# PCB.net
KiCad netlist of a schematic drawn in EasyEDA Pro
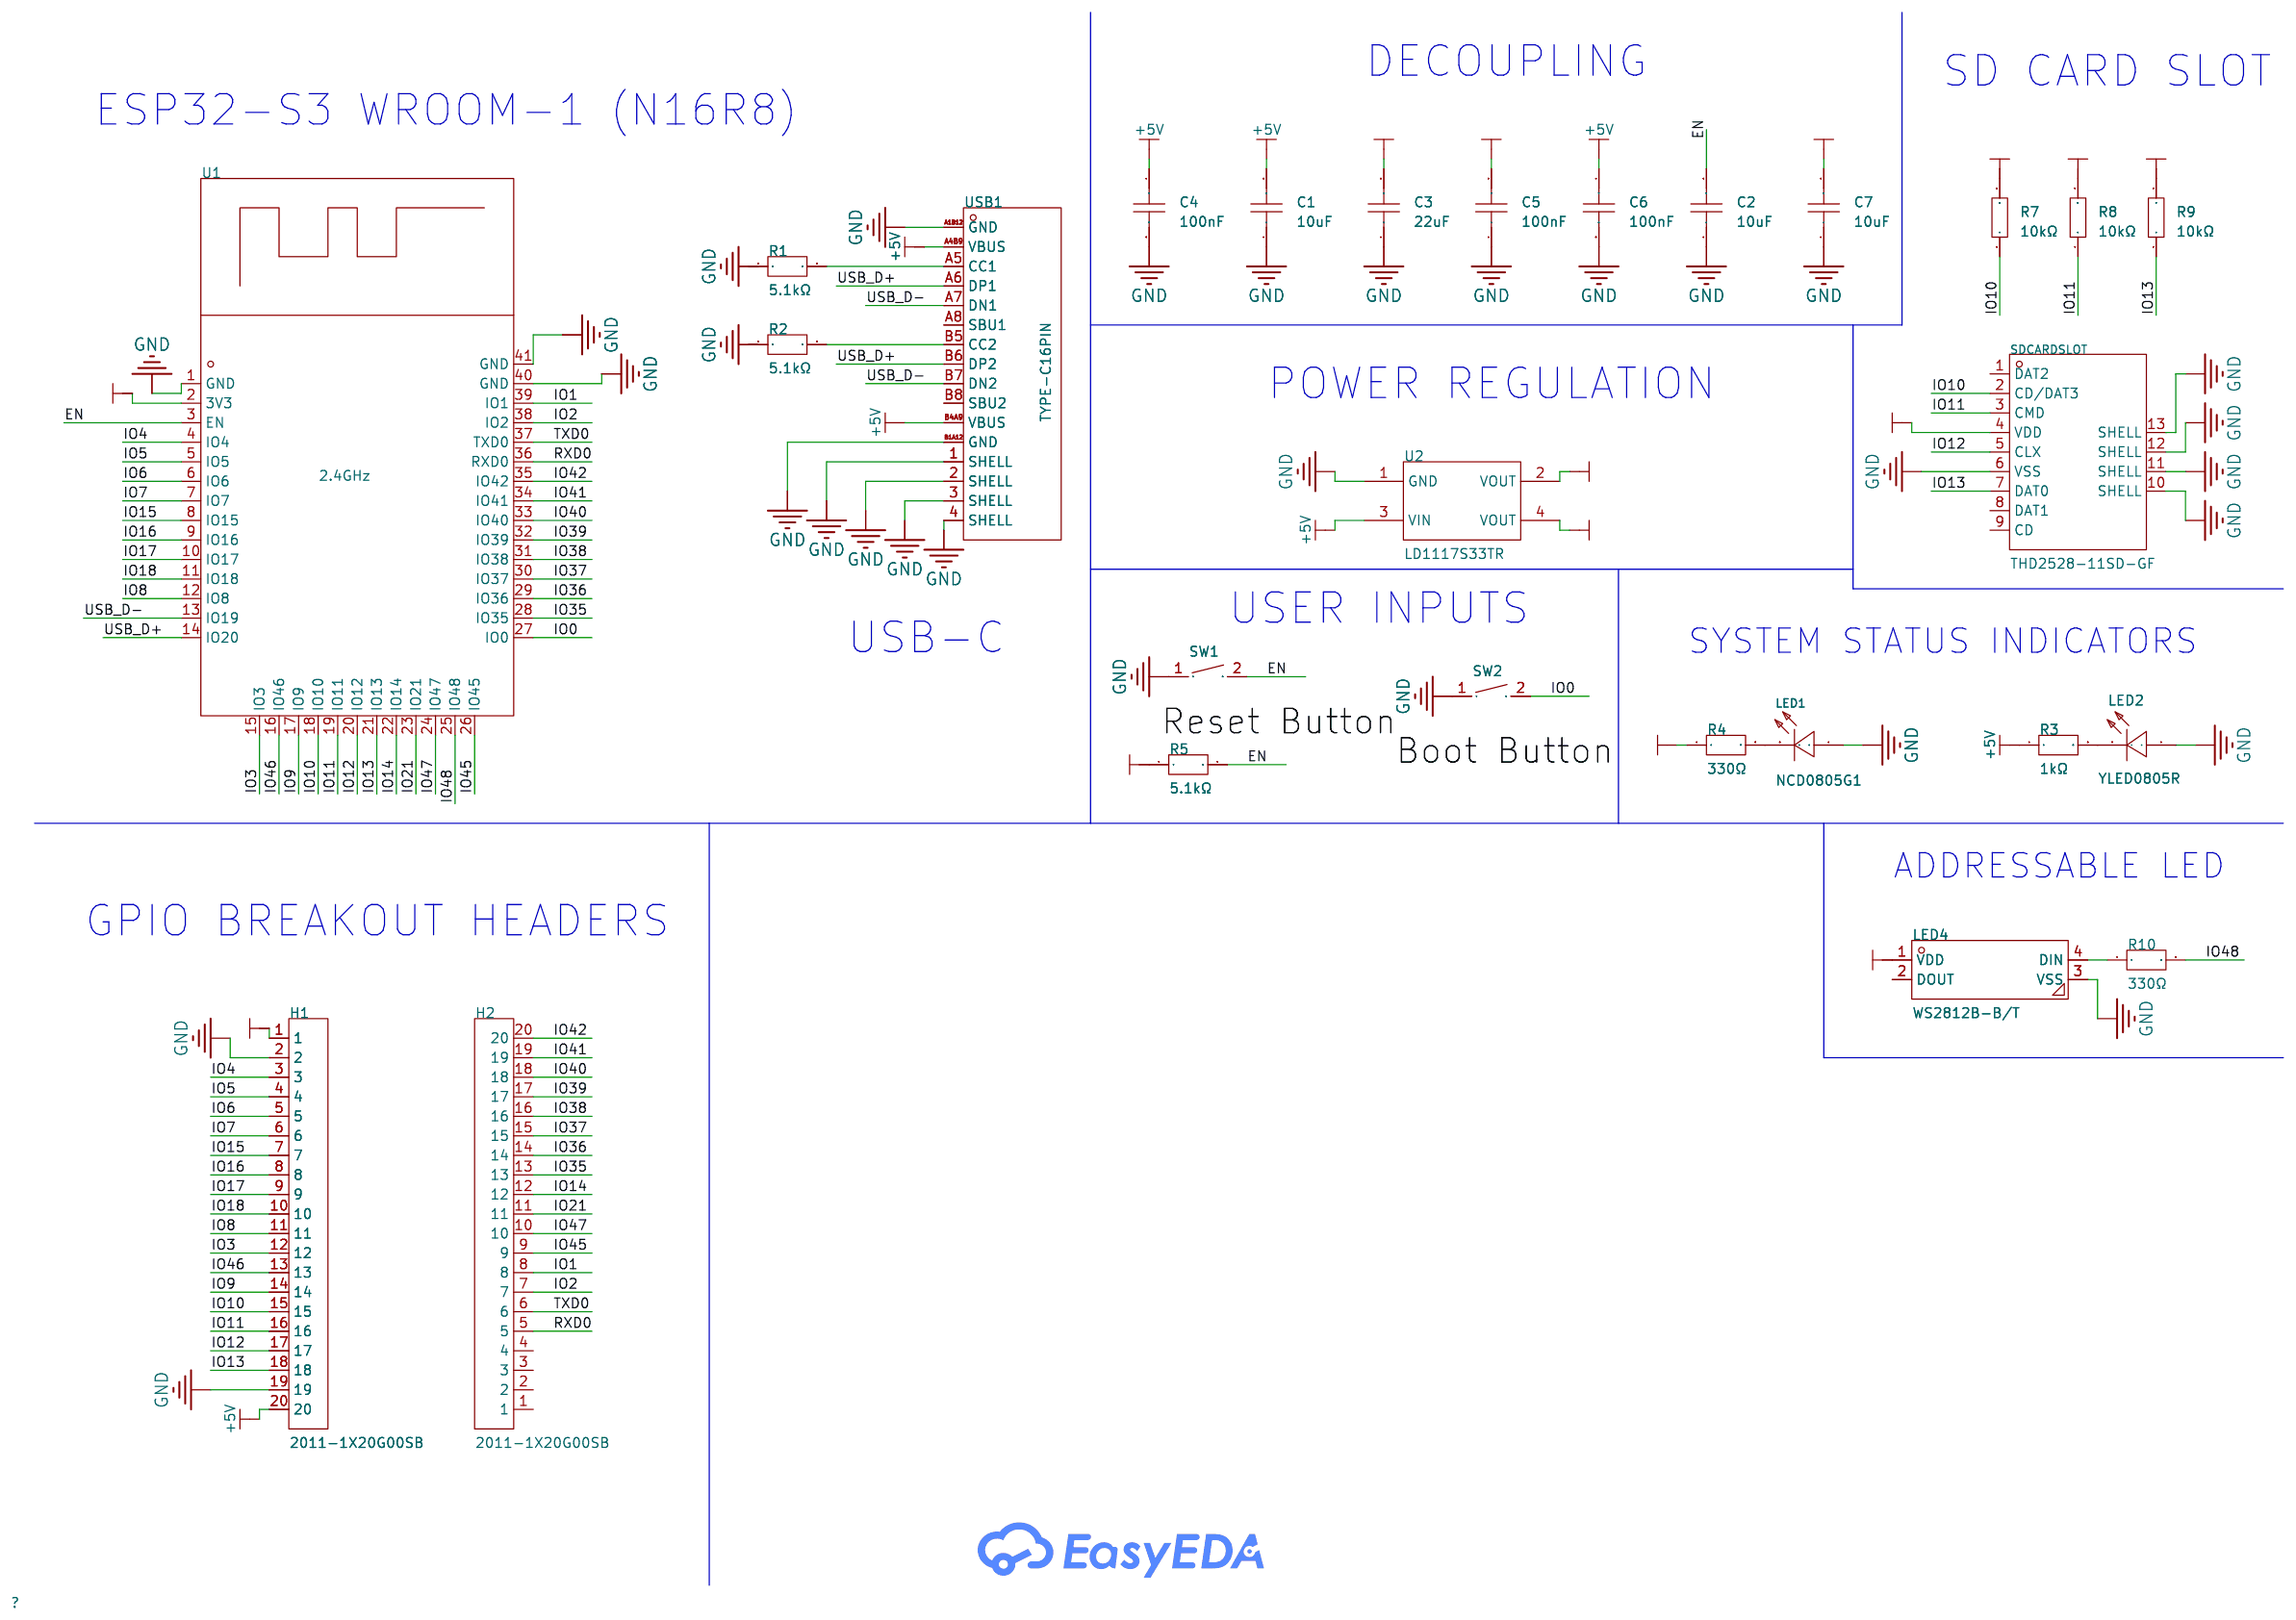
[diagram p0: schematic sheet]

(export (version "E")
  (design (tool "Eeschema 10.0.6"))
  (components
    (comp (ref "C1")
      (value "10uF")
      (footprint "easyedapro:C0603")
      (description "Capacitance:10uF Tolerance:±10% Tolerance:±10% Voltage Rating:10V Temperature Coefficient:X5R")
      (fields
        (field (name "Manufacturer Part") "CL10A106KP8NNNC")
        (field (name "Manufacturer") "SAMSUNG(三星)")
      )
      (libsource (lib "easyedapro") (part "CL10A106KP8NNNC"))
    )
    (comp (ref "C2")
      (value "10uF")
      (footprint "easyedapro:C0603")
      (description "Capacitance:10uF Tolerance:±10% Tolerance:±10% Voltage Rating:10V Temperature Coefficient:X5R")
      (fields
        (field (name "Manufacturer Part") "CL10A106KP8NNNC")
        (field (name "Manufacturer") "SAMSUNG(三星)")
      )
      (libsource (lib "easyedapro") (part "CL10A106KP8NNNC"))
    )
    (comp (ref "C3")
      (value "22uF")
      (footprint "easyedapro:C0805")
      (description "Capacitance:22uF Tolerance:±20% Tolerance:±20% Voltage Rating:25V Temperature Coefficient:X5R")
      (fields
        (field (name "Manufacturer Part") "CGA0805X5R226M250MT")
        (field (name "Manufacturer") "HRE(芯声)")
      )
      (libsource (lib "easyedapro") (part "CGA0805X5R226M250MT"))
    )
    (comp (ref "C4")
      (value "100nF")
      (footprint "easyedapro:C0603")
      (description "Capacitance:100nF Tolerance:±10% Tolerance:±10% Voltage Rating:50V Temperature Coefficient:X7R")
      (fields
        (field (name "Manufacturer Part") "CC0603KRX7R9BB104")
        (field (name "Manufacturer") "YAGEO(国巨)")
      )
      (libsource (lib "easyedapro") (part "CC0603KRX7R9BB104"))
    )
    (comp (ref "C5")
      (value "100nF")
      (footprint "easyedapro:C0603")
      (description "Capacitance:100nF Tolerance:±10% Tolerance:±10% Voltage Rating:50V Temperature Coefficient:X7R")
      (fields
        (field (name "Manufacturer Part") "CC0603KRX7R9BB104")
        (field (name "Manufacturer") "YAGEO(国巨)")
      )
      (libsource (lib "easyedapro") (part "CC0603KRX7R9BB104"))
    )
    (comp (ref "C6")
      (value "100nF")
      (footprint "easyedapro:C0603")
      (description "Capacitance:100nF Tolerance:±10% Tolerance:±10% Voltage Rating:50V Temperature Coefficient:X7R")
      (fields
        (field (name "Manufacturer Part") "CC0603KRX7R9BB104")
        (field (name "Manufacturer") "YAGEO(国巨)")
      )
      (libsource (lib "easyedapro") (part "CC0603KRX7R9BB104"))
    )
    (comp (ref "C7")
      (value "10uF")
      (footprint "easyedapro:C0603")
      (description "Capacitance:10uF Tolerance:±10% Tolerance:±10% Voltage Rating:10V Temperature Coefficient:X5R")
      (fields
        (field (name "Manufacturer Part") "CL10A106KP8NNNC")
        (field (name "Manufacturer") "SAMSUNG(三星)")
      )
      (libsource (lib "easyedapro") (part "CL10A106KP8NNNC"))
    )
    (comp (ref "H1")
      (value "2011-1X20G00SB")
      (footprint "easyedapro:HDR-TH_20P-P2.54_2011-1X20G00SB")
      (fields (field (name "Manufacturer") "WingTAT(格林柏)"))
      (libsource (lib "easyedapro") (part "2011-1X20G00SB"))
    )
    (comp (ref "H2")
      (value "2011-1X20G00SB")
      (footprint "easyedapro:HDR-TH_20P-P2.54_2011-1X20G00SB")
      (fields (field (name "Manufacturer") "WingTAT(格林柏)"))
      (libsource (lib "easyedapro") (part "2011-1X20G00SB"))
    )
    (comp (ref "LED1")
      (value "NCD0805G1")
      (footprint "easyedapro:LED0805-R-RD")
      (fields (field (name "Manufacturer") "国星光电"))
      (libsource (lib "easyedapro") (part "FC-2012UGK-520D5"))
    )
    (comp (ref "LED2")
      (value "YLED0805R")
      (footprint "easyedapro:LED0805-R-RD_RED")
      (fields (field (name "Manufacturer") "YONGYUTAI(永裕泰)"))
      (libsource (lib "easyedapro") (part "YLED0805R"))
    )
    (comp (ref "LED4")
      (value "WS2812B-B/T")
      (footprint "easyedapro:LED-SMD_4P-L5.0-W5.0-TL_WS2812B-B")
      (fields (field (name "Manufacturer") "worldsemi"))
      (libsource (lib "easyedapro") (part "WS2812B-B/W"))
    )
    (comp (ref "R1")
      (value "5.1kΩ")
      (footprint "easyedapro:R0603")
      (fields (field (name "Manufacturer Part") "FRC0603F5101TS") (field (name "Manufacturer") "FOJAN(富捷)"))
      (libsource (lib "easyedapro") (part "FRC0603F5101TS"))
    )
    (comp (ref "R2")
      (value "5.1kΩ")
      (footprint "easyedapro:R0603")
      (fields (field (name "Manufacturer Part") "FRC0603F5101TS") (field (name "Manufacturer") "FOJAN(富捷)"))
      (libsource (lib "easyedapro") (part "FRC0603F5101TS"))
    )
    (comp (ref "R3")
      (value "1kΩ")
      (footprint "easyedapro:R0603")
      (fields (field (name "Manufacturer Part") "FRC0603J102 TS") (field (name "Manufacturer") "FOJAN(富捷)"))
      (libsource (lib "easyedapro") (part "FRC0603J102 TS"))
    )
    (comp (ref "R4")
      (value "330Ω")
      (footprint "easyedapro:R0603")
      (fields (field (name "Manufacturer Part") "FRC0603J331 TS") (field (name "Manufacturer") "FOJAN(富捷)"))
      (libsource (lib "easyedapro") (part "FRC0603J331 TS"))
    )
    (comp (ref "R5")
      (value "5.1kΩ")
      (footprint "easyedapro:R0603")
      (fields (field (name "Manufacturer Part") "FRC0603F5101TS") (field (name "Manufacturer") "FOJAN(富捷)"))
      (libsource (lib "easyedapro") (part "FRC0603F5101TS"))
    )
    (comp (ref "R7")
      (value "10kΩ")
      (footprint "easyedapro:R0603")
      (fields (field (name "Manufacturer Part") "RC0603FR-0710KL") (field (name "Manufacturer") "YAGEO(国巨)"))
      (libsource (lib "easyedapro") (part "RC0603FR-0710KL"))
    )
    (comp (ref "R8")
      (value "10kΩ")
      (footprint "easyedapro:R0603")
      (fields (field (name "Manufacturer Part") "RC0603FR-0710KL") (field (name "Manufacturer") "YAGEO(国巨)"))
      (libsource (lib "easyedapro") (part "RC0603FR-0710KL"))
    )
    (comp (ref "R9")
      (value "10kΩ")
      (footprint "easyedapro:R0603")
      (fields (field (name "Manufacturer Part") "RC0603FR-0710KL") (field (name "Manufacturer") "YAGEO(国巨)"))
      (libsource (lib "easyedapro") (part "RC0603FR-0710KL"))
    )
    (comp (ref "R10")
      (value "330Ω")
      (footprint "easyedapro:R0603")
      (fields (field (name "Manufacturer Part") "FRC0603J331 TS") (field (name "Manufacturer") "FOJAN(富捷)"))
      (libsource (lib "easyedapro") (part "FRC0603J331 TS"))
    )
    (comp (ref "SDCARDSLOT")
      (value "THD2528-11SD-GF")
      (footprint "easyedapro:TF-SMD_THD2528-11SD-GF")
      (fields (field (name "Manufacturer") "THD(台华达)"))
      (libsource (lib "easyedapro") (part "THD2528-11SD-GF"))
    )
    (comp (ref "SW1")
      (value "Reset Button")
      (footprint "easyedapro:KEY-SMD_L4.0-W3.0-LS4.9-1")
      (fields (field (name "Manufacturer") "hanxia(韩下)"))
      (libsource (lib "easyedapro") (part "HX 3X4X2-2P-1.6N TACTILE SWITCH"))
    )
    (comp (ref "SW2")
      (value "Boot Button")
      (footprint "easyedapro:KEY-SMD_L4.0-W3.0-LS4.9-1")
      (fields (field (name "Manufacturer") "hanxia(韩下)"))
      (libsource (lib "easyedapro") (part "HX 3X4X2-2P-1.6N TACTILE SWITCH"))
    )
    (comp (ref "U1")
      (value "2.4GHz")
      (footprint "easyedapro:WIRELM-SMD_ESP32-S3-WROOM-1")
      (fields
        (field (name "Manufacturer Part") "ESP32-S3-WROOM-1-N16")
        (field (name "Manufacturer") "ESPRESSIF(乐鑫)")
      )
      (libsource (lib "easyedapro") (part "ESP32-S3-WROOM-1(N16)"))
    )
    (comp (ref "U2")
      (value "LD1117S33TR")
      (footprint "easyedapro:SOT-223_L6.5-W3.5-P2.30-LS7.0-BR")
      (fields (field (name "Manufacturer") "ST(意法半导体)"))
      (libsource (lib "easyedapro") (part "LD1117S33TR"))
    )
    (comp (ref "USB1")
      (value "TYPE-C16PIN")
      (footprint "easyedapro:USB-C-SMD_TYPE-C16PIN")
      (fields (field (name "Manufacturer") "SHOU HAN(首韩)"))
      (libsource (lib "easyedapro") (part "TYPE-C16PIN"))
    )
  )
  (nets
    (net (code "1") (name "+3V3") (class "Default")
      (node (ref "C3") (pin "2") (pinfunction "2_2") (pintype "unspecified"))
      (node (ref "C5") (pin "2") (pinfunction "2_2") (pintype "unspecified"))
      (node (ref "C7") (pin "2") (pinfunction "2_2") (pintype "unspecified"))
      (node (ref "H1") (pin "1") (pinfunction "1_1") (pintype "unspecified"))
      (node (ref "LED4") (pin "1") (pinfunction "VDD_1") (pintype "unspecified"))
      (node (ref "R4") (pin "1") (pinfunction "1_1") (pintype "unspecified"))
      (node (ref "R5") (pin "1") (pinfunction "1_1") (pintype "unspecified"))
      (node (ref "R7") (pin "2") (pinfunction "2_2") (pintype "input"))
      (node (ref "R8") (pin "2") (pinfunction "2_2") (pintype "input"))
      (node (ref "R9") (pin "2") (pinfunction "2_2") (pintype "input"))
      (node (ref "SDCARDSLOT") (pin "4") (pinfunction "VDD_4") (pintype "input"))
      (node (ref "U1") (pin "2") (pinfunction "3V3_2") (pintype "unspecified"))
      (node (ref "U2") (pin "2") (pinfunction "VOUT_2") (pintype "unspecified"))
      (node (ref "U2") (pin "4") (pinfunction "VOUT_4") (pintype "unspecified"))
    )
    (net (code "2") (name "+5V") (class "Default")
      (node (ref "C1") (pin "2") (pinfunction "2_2") (pintype "unspecified"))
      (node (ref "C4") (pin "1") (pinfunction "1_1") (pintype "unspecified"))
      (node (ref "C6") (pin "1") (pinfunction "1_1") (pintype "unspecified"))
      (node (ref "H1") (pin "20") (pinfunction "20_20") (pintype "unspecified"))
      (node (ref "R3") (pin "1") (pinfunction "1_1") (pintype "unspecified"))
      (node (ref "U2") (pin "3") (pinfunction "VIN_3") (pintype "unspecified"))
      (node (ref "USB1") (pin "A4B9") (pinfunction "VBUS_A4B9") (pintype "unspecified"))
      (node (ref "USB1") (pin "B4A9") (pinfunction "VBUS_B4A9") (pintype "unspecified"))
    )
    (net (code "3") (name "/EN") (class "Default")
      (node (ref "C2") (pin "2") (pinfunction "2_2") (pintype "unspecified"))
      (node (ref "R5") (pin "2") (pinfunction "2_2") (pintype "unspecified"))
      (node (ref "SW1") (pin "2") (pinfunction "2_2") (pintype "unspecified"))
      (node (ref "U1") (pin "3") (pinfunction "EN_3") (pintype "unspecified"))
    )
    (net (code "4") (name "/IO0") (class "Default")
      (node (ref "SW2") (pin "2") (pinfunction "2_2") (pintype "unspecified"))
      (node (ref "U1") (pin "27") (pinfunction "IO0_27") (pintype "unspecified"))
    )
    (net (code "5") (name "/IO1") (class "Default")
      (node (ref "H2") (pin "8") (pinfunction "8_8") (pintype "unspecified"))
      (node (ref "U1") (pin "39") (pinfunction "IO1_39") (pintype "unspecified"))
    )
    (net (code "6") (name "/IO2") (class "Default")
      (node (ref "H2") (pin "7") (pinfunction "7_7") (pintype "unspecified"))
      (node (ref "U1") (pin "38") (pinfunction "IO2_38") (pintype "unspecified"))
    )
    (net (code "7") (name "/IO3") (class "Default")
      (node (ref "H1") (pin "12") (pinfunction "12_12") (pintype "unspecified"))
      (node (ref "U1") (pin "15") (pinfunction "IO3_15") (pintype "unspecified"))
    )
    (net (code "8") (name "/IO4") (class "Default")
      (node (ref "H1") (pin "3") (pinfunction "3_3") (pintype "unspecified"))
      (node (ref "U1") (pin "4") (pinfunction "IO4_4") (pintype "unspecified"))
    )
    (net (code "9") (name "/IO5") (class "Default")
      (node (ref "H1") (pin "4") (pinfunction "4_4") (pintype "unspecified"))
      (node (ref "U1") (pin "5") (pinfunction "IO5_5") (pintype "unspecified"))
    )
    (net (code "10") (name "/IO6") (class "Default")
      (node (ref "H1") (pin "5") (pinfunction "5_5") (pintype "unspecified"))
      (node (ref "U1") (pin "6") (pinfunction "IO6_6") (pintype "unspecified"))
    )
    (net (code "11") (name "/IO7") (class "Default")
      (node (ref "H1") (pin "6") (pinfunction "6_6") (pintype "unspecified"))
      (node (ref "U1") (pin "7") (pinfunction "IO7_7") (pintype "unspecified"))
    )
    (net (code "12") (name "/IO8") (class "Default")
      (node (ref "H1") (pin "11") (pinfunction "11_11") (pintype "unspecified"))
      (node (ref "U1") (pin "12") (pinfunction "IO8_12") (pintype "unspecified"))
    )
    (net (code "13") (name "/IO9") (class "Default")
      (node (ref "H1") (pin "14") (pinfunction "14_14") (pintype "unspecified"))
      (node (ref "U1") (pin "17") (pinfunction "IO9_17") (pintype "unspecified"))
    )
    (net (code "14") (name "/IO10") (class "Default")
      (node (ref "H1") (pin "15") (pinfunction "15_15") (pintype "unspecified"))
      (node (ref "R7") (pin "1") (pinfunction "1_1") (pintype "input"))
      (node (ref "SDCARDSLOT") (pin "2") (pinfunction "CD/DAT3_2") (pintype "input"))
      (node (ref "U1") (pin "18") (pinfunction "IO10_18") (pintype "unspecified"))
    )
    (net (code "15") (name "/IO11") (class "Default")
      (node (ref "H1") (pin "16") (pinfunction "16_16") (pintype "unspecified"))
      (node (ref "R8") (pin "1") (pinfunction "1_1") (pintype "input"))
      (node (ref "SDCARDSLOT") (pin "3") (pinfunction "CMD_3") (pintype "input"))
      (node (ref "U1") (pin "19") (pinfunction "IO11_19") (pintype "unspecified"))
    )
    (net (code "16") (name "/IO12") (class "Default")
      (node (ref "H1") (pin "17") (pinfunction "17_17") (pintype "unspecified"))
      (node (ref "SDCARDSLOT") (pin "5") (pinfunction "CLX_5") (pintype "input"))
      (node (ref "U1") (pin "20") (pinfunction "IO12_20") (pintype "unspecified"))
    )
    (net (code "17") (name "/IO13") (class "Default")
      (node (ref "H1") (pin "18") (pinfunction "18_18") (pintype "unspecified"))
      (node (ref "R9") (pin "1") (pinfunction "1_1") (pintype "input"))
      (node (ref "SDCARDSLOT") (pin "7") (pinfunction "DAT0_7") (pintype "input"))
      (node (ref "U1") (pin "21") (pinfunction "IO13_21") (pintype "unspecified"))
    )
    (net (code "18") (name "/IO14") (class "Default")
      (node (ref "H2") (pin "12") (pinfunction "12_12") (pintype "unspecified"))
      (node (ref "U1") (pin "22") (pinfunction "IO14_22") (pintype "unspecified"))
    )
    (net (code "19") (name "/IO15") (class "Default")
      (node (ref "H1") (pin "7") (pinfunction "7_7") (pintype "unspecified"))
      (node (ref "U1") (pin "8") (pinfunction "IO15_8") (pintype "unspecified"))
    )
    (net (code "20") (name "/IO16") (class "Default")
      (node (ref "H1") (pin "8") (pinfunction "8_8") (pintype "unspecified"))
      (node (ref "U1") (pin "9") (pinfunction "IO16_9") (pintype "unspecified"))
    )
    (net (code "21") (name "/IO17") (class "Default")
      (node (ref "H1") (pin "9") (pinfunction "9_9") (pintype "unspecified"))
      (node (ref "U1") (pin "10") (pinfunction "IO17_10") (pintype "unspecified"))
    )
    (net (code "22") (name "/IO18") (class "Default")
      (node (ref "H1") (pin "10") (pinfunction "10_10") (pintype "unspecified"))
      (node (ref "U1") (pin "11") (pinfunction "IO18_11") (pintype "unspecified"))
    )
    (net (code "23") (name "/IO21") (class "Default")
      (node (ref "H2") (pin "11") (pinfunction "11_11") (pintype "unspecified"))
      (node (ref "U1") (pin "23") (pinfunction "IO21_23") (pintype "unspecified"))
    )
    (net (code "24") (name "/IO35") (class "Default")
      (node (ref "H2") (pin "13") (pinfunction "13_13") (pintype "unspecified"))
      (node (ref "U1") (pin "28") (pinfunction "IO35_28") (pintype "unspecified"))
    )
    (net (code "25") (name "/IO36") (class "Default")
      (node (ref "H2") (pin "14") (pinfunction "14_14") (pintype "unspecified"))
      (node (ref "U1") (pin "29") (pinfunction "IO36_29") (pintype "unspecified"))
    )
    (net (code "26") (name "/IO37") (class "Default")
      (node (ref "H2") (pin "15") (pinfunction "15_15") (pintype "unspecified"))
      (node (ref "U1") (pin "30") (pinfunction "IO37_30") (pintype "unspecified"))
    )
    (net (code "27") (name "/IO38") (class "Default")
      (node (ref "H2") (pin "16") (pinfunction "16_16") (pintype "unspecified"))
      (node (ref "U1") (pin "31") (pinfunction "IO38_31") (pintype "unspecified"))
    )
    (net (code "28") (name "/IO39") (class "Default")
      (node (ref "H2") (pin "17") (pinfunction "17_17") (pintype "unspecified"))
      (node (ref "U1") (pin "32") (pinfunction "IO39_32") (pintype "unspecified"))
    )
    (net (code "29") (name "/IO40") (class "Default")
      (node (ref "H2") (pin "18") (pinfunction "18_18") (pintype "unspecified"))
      (node (ref "U1") (pin "33") (pinfunction "IO40_33") (pintype "unspecified"))
    )
    (net (code "30") (name "/IO41") (class "Default")
      (node (ref "H2") (pin "19") (pinfunction "19_19") (pintype "unspecified"))
      (node (ref "U1") (pin "34") (pinfunction "IO41_34") (pintype "unspecified"))
    )
    (net (code "31") (name "/IO42") (class "Default")
      (node (ref "H2") (pin "20") (pinfunction "20_20") (pintype "unspecified"))
      (node (ref "U1") (pin "35") (pinfunction "IO42_35") (pintype "unspecified"))
    )
    (net (code "32") (name "/IO45") (class "Default")
      (node (ref "H2") (pin "9") (pinfunction "9_9") (pintype "unspecified"))
      (node (ref "U1") (pin "26") (pinfunction "IO45_26") (pintype "unspecified"))
    )
    (net (code "33") (name "/IO46") (class "Default")
      (node (ref "H1") (pin "13") (pinfunction "13_13") (pintype "unspecified"))
      (node (ref "U1") (pin "16") (pinfunction "IO46_16") (pintype "unspecified"))
    )
    (net (code "34") (name "/IO47") (class "Default")
      (node (ref "H2") (pin "10") (pinfunction "10_10") (pintype "unspecified"))
      (node (ref "U1") (pin "24") (pinfunction "IO47_24") (pintype "unspecified"))
    )
    (net (code "35") (name "/IO48") (class "Default")
      (node (ref "R10") (pin "2") (pinfunction "2_2") (pintype "unspecified"))
      (node (ref "U1") (pin "25") (pinfunction "IO48_25") (pintype "unspecified"))
    )
    (net (code "36") (name "/RXD0") (class "Default")
      (node (ref "H2") (pin "5") (pinfunction "5_5") (pintype "unspecified"))
      (node (ref "U1") (pin "36") (pinfunction "RXD0_36") (pintype "unspecified"))
    )
    (net (code "37") (name "/TXD0") (class "Default")
      (node (ref "H2") (pin "6") (pinfunction "6_6") (pintype "unspecified"))
      (node (ref "U1") (pin "37") (pinfunction "TXD0_37") (pintype "unspecified"))
    )
    (net (code "38") (name "/USB_D+") (class "Default")
      (node (ref "U1") (pin "14") (pinfunction "IO20_14") (pintype "unspecified"))
      (node (ref "USB1") (pin "A6") (pinfunction "DP1_A6") (pintype "unspecified"))
      (node (ref "USB1") (pin "B6") (pinfunction "DP2_B6") (pintype "unspecified"))
    )
    (net (code "39") (name "/USB_D-") (class "Default")
      (node (ref "U1") (pin "13") (pinfunction "IO19_13") (pintype "unspecified"))
      (node (ref "USB1") (pin "A7") (pinfunction "DN1_A7") (pintype "unspecified"))
      (node (ref "USB1") (pin "B7") (pinfunction "DN2_B7") (pintype "unspecified"))
    )
    (net (code "40") (name "GND") (class "Default")
      (node (ref "C1") (pin "1") (pinfunction "1_1") (pintype "unspecified"))
      (node (ref "C2") (pin "1") (pinfunction "1_1") (pintype "unspecified"))
      (node (ref "C3") (pin "1") (pinfunction "1_1") (pintype "unspecified"))
      (node (ref "C4") (pin "2") (pinfunction "2_2") (pintype "unspecified"))
      (node (ref "C5") (pin "1") (pinfunction "1_1") (pintype "unspecified"))
      (node (ref "C6") (pin "2") (pinfunction "2_2") (pintype "unspecified"))
      (node (ref "C7") (pin "1") (pinfunction "1_1") (pintype "unspecified"))
      (node (ref "H1") (pin "19") (pinfunction "19_19") (pintype "unspecified"))
      (node (ref "H1") (pin "2") (pinfunction "2_2") (pintype "unspecified"))
      (node (ref "LED1") (pin "1") (pinfunction "A_1") (pintype "input"))
      (node (ref "LED2") (pin "1") (pinfunction "+_1") (pintype "unspecified"))
      (node (ref "LED4") (pin "3") (pinfunction "VSS_3") (pintype "unspecified"))
      (node (ref "R1") (pin "1") (pinfunction "1_1") (pintype "unspecified"))
      (node (ref "R2") (pin "1") (pinfunction "1_1") (pintype "unspecified"))
      (node (ref "SDCARDSLOT") (pin "10") (pinfunction "SHELL_10") (pintype "input"))
      (node (ref "SDCARDSLOT") (pin "11") (pinfunction "SHELL_11") (pintype "input"))
      (node (ref "SDCARDSLOT") (pin "12") (pinfunction "SHELL_12") (pintype "input"))
      (node (ref "SDCARDSLOT") (pin "13") (pinfunction "SHELL_13") (pintype "input"))
      (node (ref "SDCARDSLOT") (pin "6") (pinfunction "VSS_6") (pintype "input"))
      (node (ref "SW1") (pin "1") (pinfunction "1_1") (pintype "unspecified"))
      (node (ref "SW2") (pin "1") (pinfunction "1_1") (pintype "unspecified"))
      (node (ref "U1") (pin "1") (pinfunction "GND_1") (pintype "unspecified"))
      (node (ref "U1") (pin "40") (pinfunction "GND_40") (pintype "unspecified"))
      (node (ref "U1") (pin "41") (pinfunction "GND_41") (pintype "unspecified"))
      (node (ref "U2") (pin "1") (pinfunction "GND_1") (pintype "unspecified"))
      (node (ref "USB1") (pin "1") (pinfunction "SHELL_1") (pintype "unspecified"))
      (node (ref "USB1") (pin "2") (pinfunction "SHELL_2") (pintype "unspecified"))
      (node (ref "USB1") (pin "3") (pinfunction "SHELL_3") (pintype "unspecified"))
      (node (ref "USB1") (pin "4") (pinfunction "SHELL_4") (pintype "unspecified"))
      (node (ref "USB1") (pin "A1B12") (pinfunction "GND_A1B12") (pintype "unspecified"))
      (node (ref "USB1") (pin "B1A12") (pinfunction "GND_B1A12") (pintype "unspecified"))
    )
    (net (code "41") (name "Net-(LED1-K)") (class "Default")
      (node (ref "LED1") (pin "2") (pinfunction "K_2") (pintype "input"))
      (node (ref "R4") (pin "2") (pinfunction "2_2") (pintype "unspecified"))
    )
    (net (code "42") (name "Net-(LED2--)") (class "Default")
      (node (ref "LED2") (pin "2") (pinfunction "-_2") (pintype "unspecified"))
      (node (ref "R3") (pin "2") (pinfunction "2_2") (pintype "unspecified"))
    )
    (net (code "43") (name "Net-(LED4-DIN)") (class "Default")
      (node (ref "LED4") (pin "4") (pinfunction "DIN_4") (pintype "unspecified"))
      (node (ref "R10") (pin "1") (pinfunction "1_1") (pintype "unspecified"))
    )
    (net (code "44") (name "Net-(USB1-CC1)") (class "Default")
      (node (ref "R1") (pin "2") (pinfunction "2_2") (pintype "unspecified"))
      (node (ref "USB1") (pin "A5") (pinfunction "CC1_A5") (pintype "unspecified"))
    )
    (net (code "45") (name "Net-(USB1-CC2)") (class "Default")
      (node (ref "R2") (pin "2") (pinfunction "2_2") (pintype "unspecified"))
      (node (ref "USB1") (pin "B5") (pinfunction "CC2_B5") (pintype "unspecified"))
    )
    (net (code "46") (name "unconnected-(H2-Pad1)") (class "Default")
      (node (ref "H2") (pin "1") (pinfunction "1_1") (pintype "unspecified"))
    )
    (net (code "47") (name "unconnected-(H2-Pad2)") (class "Default")
      (node (ref "H2") (pin "2") (pinfunction "2_2") (pintype "unspecified"))
    )
    (net (code "48") (name "unconnected-(H2-Pad3)") (class "Default")
      (node (ref "H2") (pin "3") (pinfunction "3_3") (pintype "unspecified"))
    )
    (net (code "49") (name "unconnected-(H2-Pad4)") (class "Default")
      (node (ref "H2") (pin "4") (pinfunction "4_4") (pintype "unspecified"))
    )
    (net (code "50") (name "unconnected-(LED4-DOUT-Pad2)") (class "Default")
      (node (ref "LED4") (pin "2") (pinfunction "DOUT_2") (pintype "unspecified"))
    )
    (net (code "51") (name "unconnected-(SDCARDSLOT-CD-Pad9)") (class "Default")
      (node (ref "SDCARDSLOT") (pin "9") (pinfunction "CD_9") (pintype "input"))
    )
    (net (code "52") (name "unconnected-(SDCARDSLOT-DAT1-Pad8)") (class "Default")
      (node (ref "SDCARDSLOT") (pin "8") (pinfunction "DAT1_8") (pintype "input"))
    )
    (net (code "53") (name "unconnected-(SDCARDSLOT-DAT2-Pad1)") (class "Default")
      (node (ref "SDCARDSLOT") (pin "1") (pinfunction "DAT2_1") (pintype "input"))
    )
    (net (code "54") (name "unconnected-(USB1-SBU1-PadA8)") (class "Default")
      (node (ref "USB1") (pin "A8") (pinfunction "SBU1_A8") (pintype "unspecified"))
    )
    (net (code "55") (name "unconnected-(USB1-SBU2-PadB8)") (class "Default")
      (node (ref "USB1") (pin "B8") (pinfunction "SBU2_B8") (pintype "unspecified"))
    )
  )
)
